# placa_v1.net
KiCad netlist of a schematic drawn in EAGLE
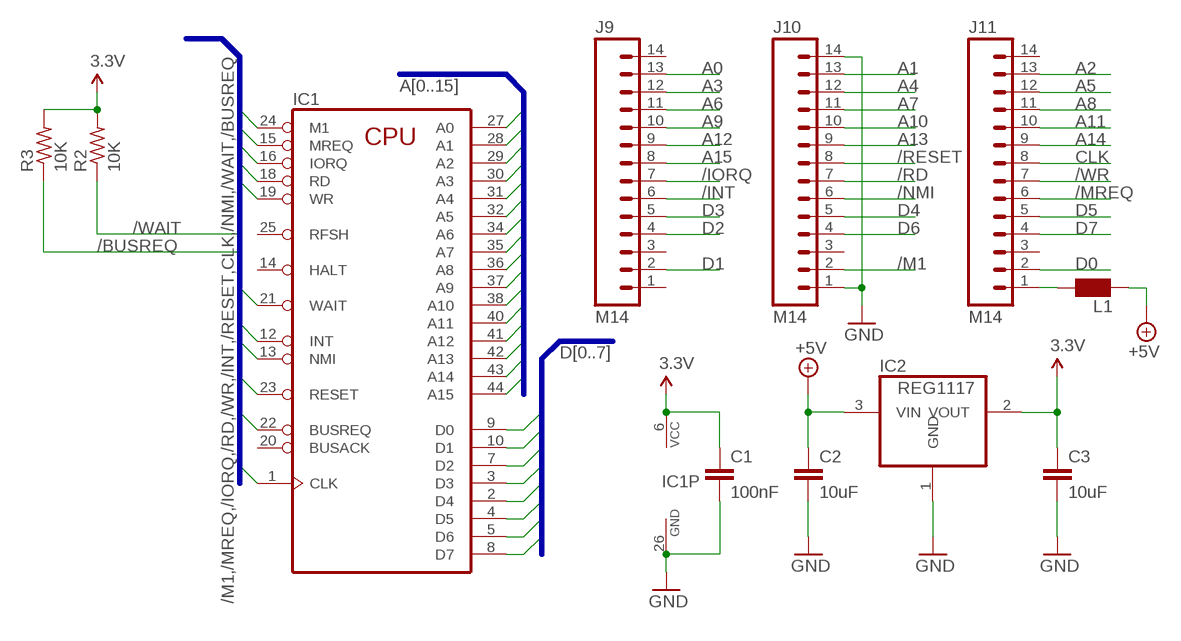
[diagram p0: schematic, sheet 1]

(export (version "E")
  (design (tool "Eeschema 10.0.6"))
  (components
    (comp (ref "C1")
      (value "100nF")
      (footprint "eagle-import:C0805K")
      (libsource (lib "eagle-import") (part "C-EUC0805K"))
    )
    (comp (ref "C2")
      (value "10uF")
      (footprint "eagle-import:C0805K")
      (libsource (lib "eagle-import") (part "C-EUC0805K"))
    )
    (comp (ref "C3")
      (value "10uF")
      (footprint "eagle-import:C0805K")
      (libsource (lib "eagle-import") (part "C-EUC0805K"))
    )
    (comp (ref "IC1")
      (value "Z80CPU-F")
      (footprint "eagle-import:QFP-44")
      (libsource (lib "eagle-import") (part "Z80CPU-F"))
    )
    (comp (ref "IC2")
      (value "REG1117")
      (footprint "eagle-import:SOT223")
      (libsource (lib "eagle-import") (part "REG1117"))
    )
    (comp (ref "J9")
      (value "M14")
      (footprint "eagle-import:1X14")
      (libsource (lib "eagle-import") (part "M14"))
    )
    (comp (ref "J10")
      (value "M14")
      (footprint "eagle-import:1X14")
      (libsource (lib "eagle-import") (part "M14"))
    )
    (comp (ref "J11")
      (value "M14")
      (footprint "eagle-import:1X14")
      (libsource (lib "eagle-import") (part "M14"))
    )
    (comp (ref "L1")
      (value "WE-CBF_0805")
      (footprint "eagle-import:0805")
      (libsource (lib "eagle-import") (part "WE-CBF_0805"))
    )
    (comp (ref "R2")
      (value "10K")
      (footprint "eagle-import:R0805")
      (libsource (lib "eagle-import") (part "R-US_R0805"))
    )
    (comp (ref "R3")
      (value "10K")
      (footprint "eagle-import:R0805")
      (libsource (lib "eagle-import") (part "R-US_R0805"))
    )
  )
  (nets
    (net (code "1") (name "+5V") (class "Default")
      (node (ref "C2") (pin "1") (pinfunction "1_1") (pintype "passive"))
      (node (ref "IC2") (pin "3") (pinfunction "VIN_3") (pintype "input"))
      (node (ref "L1") (pin "2") (pinfunction "2_2") (pintype "passive"))
    )
    (net (code "2") (name "/A0") (class "Default")
      (node (ref "IC1") (pin "27") (pinfunction "A0_27") (pintype "output"))
      (node (ref "J9") (pin "13") (pinfunction "13_13") (pintype "passive"))
    )
    (net (code "3") (name "/A1") (class "Default")
      (node (ref "IC1") (pin "28") (pinfunction "A1_28") (pintype "output"))
      (node (ref "J10") (pin "13") (pinfunction "13_13") (pintype "passive"))
    )
    (net (code "4") (name "/A2") (class "Default")
      (node (ref "IC1") (pin "29") (pinfunction "A2_29") (pintype "output"))
      (node (ref "J11") (pin "13") (pinfunction "13_13") (pintype "passive"))
    )
    (net (code "5") (name "/A3") (class "Default")
      (node (ref "IC1") (pin "30") (pinfunction "A3_30") (pintype "output"))
      (node (ref "J9") (pin "12") (pinfunction "12_12") (pintype "passive"))
    )
    (net (code "6") (name "/A4") (class "Default")
      (node (ref "IC1") (pin "31") (pinfunction "A4_31") (pintype "output"))
      (node (ref "J10") (pin "12") (pinfunction "12_12") (pintype "passive"))
    )
    (net (code "7") (name "/A5") (class "Default")
      (node (ref "IC1") (pin "32") (pinfunction "A5_32") (pintype "output"))
      (node (ref "J11") (pin "12") (pinfunction "12_12") (pintype "passive"))
    )
    (net (code "8") (name "/A6") (class "Default")
      (node (ref "IC1") (pin "34") (pinfunction "A6_34") (pintype "output"))
      (node (ref "J9") (pin "11") (pinfunction "11_11") (pintype "passive"))
    )
    (net (code "9") (name "/A7") (class "Default")
      (node (ref "IC1") (pin "35") (pinfunction "A7_35") (pintype "output"))
      (node (ref "J10") (pin "11") (pinfunction "11_11") (pintype "passive"))
    )
    (net (code "10") (name "/A8") (class "Default")
      (node (ref "IC1") (pin "36") (pinfunction "A8_36") (pintype "output"))
      (node (ref "J11") (pin "11") (pinfunction "11_11") (pintype "passive"))
    )
    (net (code "11") (name "/A9") (class "Default")
      (node (ref "IC1") (pin "37") (pinfunction "A9_37") (pintype "output"))
      (node (ref "J9") (pin "10") (pinfunction "10_10") (pintype "passive"))
    )
    (net (code "12") (name "/A10") (class "Default")
      (node (ref "IC1") (pin "38") (pinfunction "A10_38") (pintype "output"))
      (node (ref "J10") (pin "10") (pinfunction "10_10") (pintype "passive"))
    )
    (net (code "13") (name "/A11") (class "Default")
      (node (ref "IC1") (pin "40") (pinfunction "A11_40") (pintype "output"))
      (node (ref "J11") (pin "10") (pinfunction "10_10") (pintype "passive"))
    )
    (net (code "14") (name "/A12") (class "Default")
      (node (ref "IC1") (pin "41") (pinfunction "A12_41") (pintype "output"))
      (node (ref "J9") (pin "9") (pinfunction "9_9") (pintype "passive"))
    )
    (net (code "15") (name "/A13") (class "Default")
      (node (ref "IC1") (pin "42") (pinfunction "A13_42") (pintype "output"))
      (node (ref "J10") (pin "9") (pinfunction "9_9") (pintype "passive"))
    )
    (net (code "16") (name "/A14") (class "Default")
      (node (ref "IC1") (pin "43") (pinfunction "A14_43") (pintype "output"))
      (node (ref "J11") (pin "9") (pinfunction "9_9") (pintype "passive"))
    )
    (net (code "17") (name "/A15") (class "Default")
      (node (ref "IC1") (pin "44") (pinfunction "A15_44") (pintype "output"))
      (node (ref "J9") (pin "8") (pinfunction "8_8") (pintype "passive"))
    )
    (net (code "19") (name "/CLK") (class "Default")
      (node (ref "IC1") (pin "1") (pinfunction "CLK_1") (pintype "input"))
      (node (ref "J11") (pin "8") (pinfunction "8_8") (pintype "passive"))
    )
    (net (code "20") (name "/D0") (class "Default")
      (node (ref "IC1") (pin "9") (pinfunction "D0_9") (pintype "bidirectional"))
      (node (ref "J11") (pin "2") (pinfunction "2_2") (pintype "passive"))
    )
    (net (code "21") (name "/D1") (class "Default")
      (node (ref "IC1") (pin "10") (pinfunction "D1_10") (pintype "bidirectional"))
      (node (ref "J9") (pin "2") (pinfunction "2_2") (pintype "passive"))
    )
    (net (code "22") (name "/D2") (class "Default")
      (node (ref "IC1") (pin "7") (pinfunction "D2_7") (pintype "bidirectional"))
      (node (ref "J9") (pin "4") (pinfunction "4_4") (pintype "passive"))
    )
    (net (code "23") (name "/D3") (class "Default")
      (node (ref "IC1") (pin "3") (pinfunction "D3_3") (pintype "bidirectional"))
      (node (ref "J9") (pin "5") (pinfunction "5_5") (pintype "passive"))
    )
    (net (code "24") (name "/D4") (class "Default")
      (node (ref "IC1") (pin "2") (pinfunction "D4_2") (pintype "bidirectional"))
      (node (ref "J10") (pin "5") (pinfunction "5_5") (pintype "passive"))
    )
    (net (code "25") (name "/D5") (class "Default")
      (node (ref "IC1") (pin "4") (pinfunction "D5_4") (pintype "bidirectional"))
      (node (ref "J11") (pin "5") (pinfunction "5_5") (pintype "passive"))
    )
    (net (code "26") (name "/D6") (class "Default")
      (node (ref "IC1") (pin "5") (pinfunction "D6_5") (pintype "bidirectional"))
      (node (ref "J10") (pin "4") (pinfunction "4_4") (pintype "passive"))
    )
    (net (code "27") (name "/D7") (class "Default")
      (node (ref "IC1") (pin "8") (pinfunction "D7_8") (pintype "bidirectional"))
      (node (ref "J11") (pin "4") (pinfunction "4_4") (pintype "passive"))
    )
    (net (code "29") (name "/{slash}BUSREQ") (class "Default")
      (node (ref "IC1") (pin "22") (pinfunction "BUSREQ_22") (pintype "input"))
      (node (ref "R3") (pin "1") (pinfunction "1_1") (pintype "passive"))
    )
    (net (code "30") (name "/{slash}INT") (class "Default")
      (node (ref "IC1") (pin "12") (pinfunction "INT_12") (pintype "input"))
      (node (ref "J9") (pin "6") (pinfunction "6_6") (pintype "passive"))
    )
    (net (code "31") (name "/{slash}IORQ") (class "Default")
      (node (ref "IC1") (pin "16") (pinfunction "IORQ_16") (pintype "output"))
      (node (ref "J9") (pin "7") (pinfunction "7_7") (pintype "passive"))
    )
    (net (code "32") (name "/{slash}M1") (class "Default")
      (node (ref "IC1") (pin "24") (pinfunction "M1_24") (pintype "output"))
      (node (ref "J10") (pin "2") (pinfunction "2_2") (pintype "passive"))
    )
    (net (code "33") (name "/{slash}MREQ") (class "Default")
      (node (ref "IC1") (pin "15") (pinfunction "MREQ_15") (pintype "output"))
      (node (ref "J11") (pin "6") (pinfunction "6_6") (pintype "passive"))
    )
    (net (code "34") (name "/{slash}NMI") (class "Default")
      (node (ref "IC1") (pin "13") (pinfunction "NMI_13") (pintype "input"))
      (node (ref "J10") (pin "6") (pinfunction "6_6") (pintype "passive"))
    )
    (net (code "35") (name "/{slash}RD") (class "Default")
      (node (ref "IC1") (pin "18") (pinfunction "RD_18") (pintype "output"))
      (node (ref "J10") (pin "7") (pinfunction "7_7") (pintype "passive"))
    )
    (net (code "36") (name "/{slash}RESET") (class "Default")
      (node (ref "IC1") (pin "23") (pinfunction "RESET_23") (pintype "input"))
      (node (ref "J10") (pin "8") (pinfunction "8_8") (pintype "passive"))
    )
    (net (code "37") (name "/{slash}WAIT") (class "Default")
      (node (ref "IC1") (pin "21") (pinfunction "WAIT_21") (pintype "input"))
      (node (ref "R2") (pin "1") (pinfunction "1_1") (pintype "passive"))
    )
    (net (code "38") (name "/{slash}WR") (class "Default")
      (node (ref "IC1") (pin "19") (pinfunction "WR_19") (pintype "output"))
      (node (ref "J11") (pin "7") (pinfunction "7_7") (pintype "passive"))
    )
    (net (code "40") (name "3.3V") (class "Default")
      (node (ref "C1") (pin "1") (pinfunction "1_1") (pintype "passive"))
      (node (ref "C3") (pin "1") (pinfunction "1_1") (pintype "passive"))
      (node (ref "IC1") (pin "6") (pinfunction "VCC_6") (pintype "power_in"))
      (node (ref "IC2") (pin "2") (pinfunction "VOUT_2") (pintype "output"))
      (node (ref "R2") (pin "2") (pinfunction "2_2") (pintype "passive"))
      (node (ref "R3") (pin "2") (pinfunction "2_2") (pintype "passive"))
    )
    (net (code "41") (name "GND") (class "Default")
      (node (ref "C1") (pin "2") (pinfunction "2_2") (pintype "passive"))
      (node (ref "C2") (pin "2") (pinfunction "2_2") (pintype "passive"))
      (node (ref "C3") (pin "2") (pinfunction "2_2") (pintype "passive"))
      (node (ref "IC1") (pin "26") (pinfunction "GND_26") (pintype "power_in"))
      (node (ref "IC2") (pin "1") (pinfunction "GND_1") (pintype "power_in"))
      (node (ref "J10") (pin "1") (pinfunction "1_1") (pintype "passive"))
      (node (ref "J10") (pin "14") (pinfunction "14_14") (pintype "passive"))
    )
    (net (code "42") (name "Net-(J11-Pad1)") (class "Default")
      (node (ref "J11") (pin "1") (pinfunction "1_1") (pintype "passive"))
      (node (ref "L1") (pin "1") (pinfunction "1_1") (pintype "passive"))
    )
    (net (code "43") (name "unconnected-(IC1A-BUSACK-Pad20)") (class "Default")
      (node (ref "IC1") (pin "20") (pinfunction "BUSACK_20") (pintype "output"))
    )
    (net (code "44") (name "unconnected-(IC1A-HALT-Pad14)") (class "Default")
      (node (ref "IC1") (pin "14") (pinfunction "HALT_14") (pintype "output"))
    )
    (net (code "45") (name "unconnected-(IC1A-RFSH-Pad25)") (class "Default")
      (node (ref "IC1") (pin "25") (pinfunction "RFSH_25") (pintype "output"))
    )
    (net (code "46") (name "unconnected-(J9-Pad1)") (class "Default")
      (node (ref "J9") (pin "1") (pinfunction "1_1") (pintype "passive"))
    )
    (net (code "47") (name "unconnected-(J9-Pad3)") (class "Default")
      (node (ref "J9") (pin "3") (pinfunction "3_3") (pintype "passive"))
    )
    (net (code "48") (name "unconnected-(J9-Pad14)") (class "Default")
      (node (ref "J9") (pin "14") (pinfunction "14_14") (pintype "passive"))
    )
    (net (code "49") (name "unconnected-(J10-Pad3)") (class "Default")
      (node (ref "J10") (pin "3") (pinfunction "3_3") (pintype "passive"))
    )
    (net (code "50") (name "unconnected-(J11-Pad3)") (class "Default")
      (node (ref "J11") (pin "3") (pinfunction "3_3") (pintype "passive"))
    )
    (net (code "51") (name "unconnected-(J11-Pad14)") (class "Default")
      (node (ref "J11") (pin "14") (pinfunction "14_14") (pintype "passive"))
    )
  )
)
